# 8x8matrix.net
KiCad netlist of a schematic drawn in EAGLE
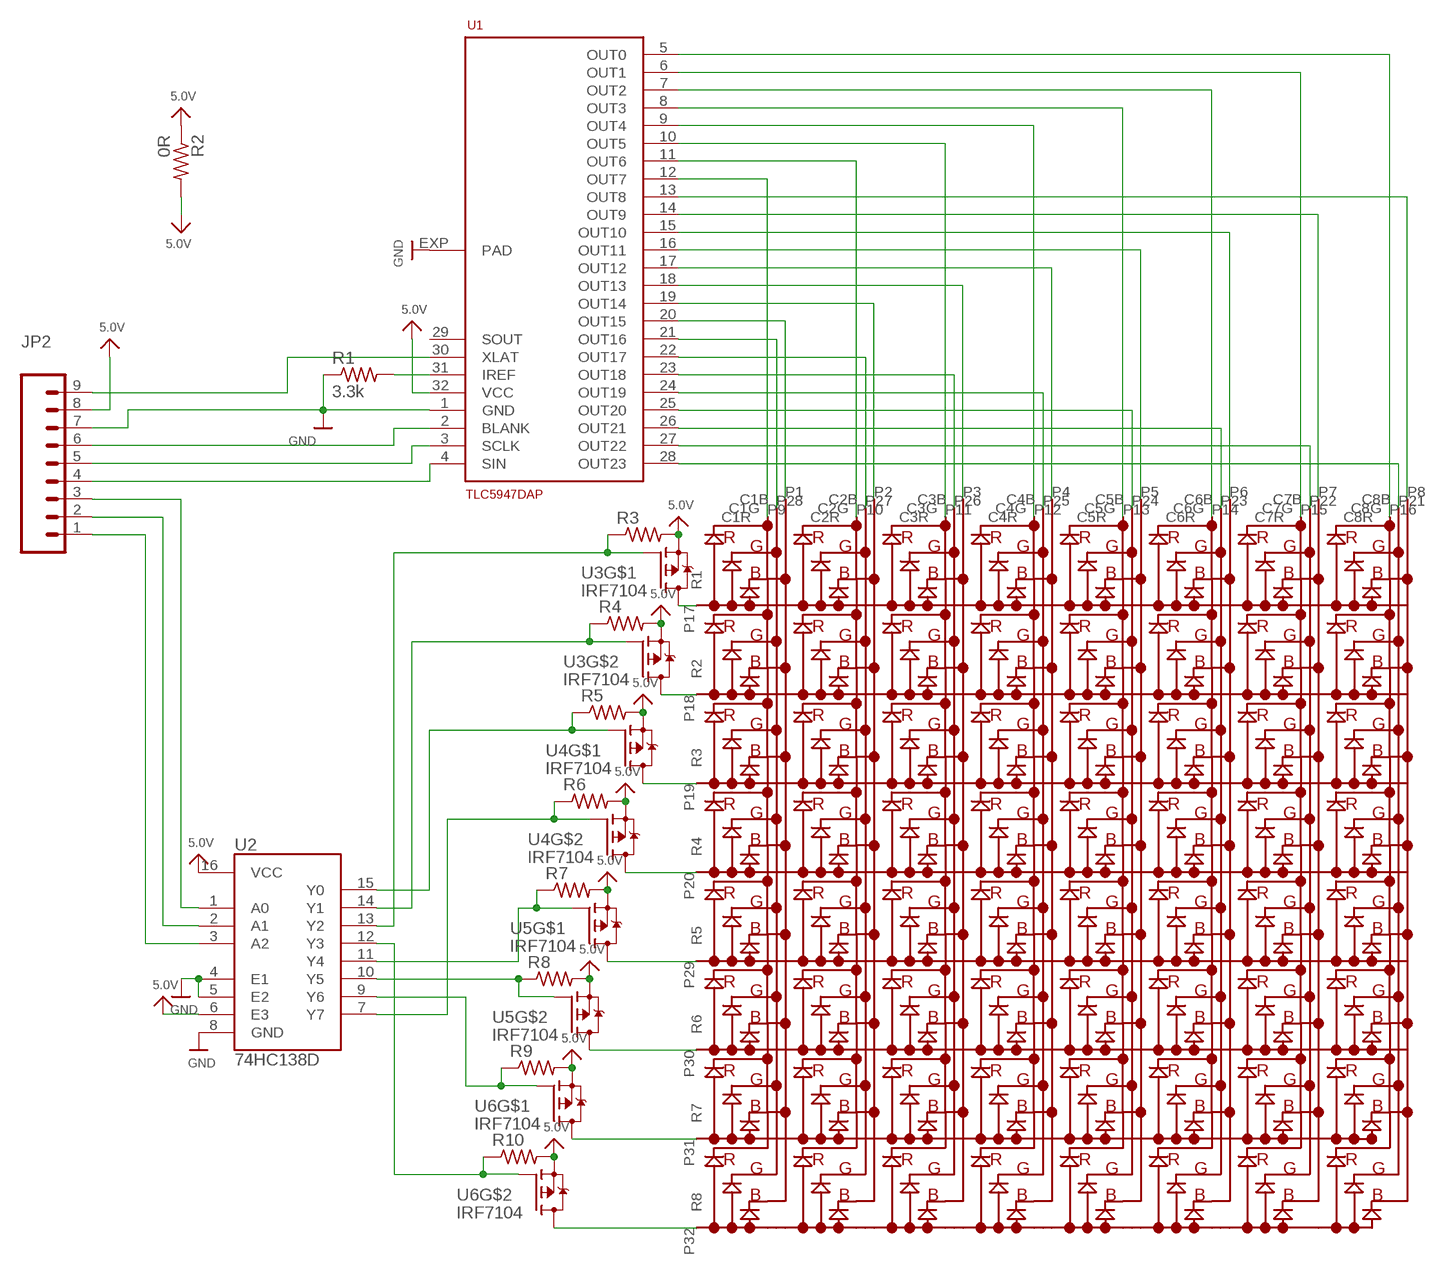
[diagram p0: schematic, sheet 1]

(export (version "E")
  (design (tool "Eeschema 10.0.6"))
  (components
    (comp (ref "JP2")
      (value "M09")
      (footprint "eagle-import:1X09")
      (libsource (lib "eagle-import") (part "M09"))
    )
    (comp (ref "R1")
      (value "3.3k")
      (footprint "eagle-import:R0805")
      (libsource (lib "eagle-import") (part "R-US_R0805"))
    )
    (comp (ref "R2")
      (value "0R")
      (footprint "eagle-import:M1206")
      (libsource (lib "eagle-import") (part "R-US_M1206"))
    )
    (comp (ref "R3")
      (value "R-US_R0805")
      (footprint "eagle-import:R0805")
      (libsource (lib "eagle-import") (part "R-US_R0805"))
    )
    (comp (ref "R4")
      (value "R-US_R0805")
      (footprint "eagle-import:R0805")
      (libsource (lib "eagle-import") (part "R-US_R0805"))
    )
    (comp (ref "R5")
      (value "R-US_R0805")
      (footprint "eagle-import:R0805")
      (libsource (lib "eagle-import") (part "R-US_R0805"))
    )
    (comp (ref "R6")
      (value "R-US_R0805")
      (footprint "eagle-import:R0805")
      (libsource (lib "eagle-import") (part "R-US_R0805"))
    )
    (comp (ref "R7")
      (value "R-US_R0805")
      (footprint "eagle-import:R0805")
      (libsource (lib "eagle-import") (part "R-US_R0805"))
    )
    (comp (ref "R8")
      (value "R-US_R0805")
      (footprint "eagle-import:R0805")
      (libsource (lib "eagle-import") (part "R-US_R0805"))
    )
    (comp (ref "R9")
      (value "R-US_R0805")
      (footprint "eagle-import:R0805")
      (libsource (lib "eagle-import") (part "R-US_R0805"))
    )
    (comp (ref "R10")
      (value "R-US_R0805")
      (footprint "eagle-import:R0805")
      (libsource (lib "eagle-import") (part "R-US_R0805"))
    )
    (comp (ref "U$1")
      (value "GTM2088ARGB")
      (footprint "eagle-import:8X8MATRIX")
      (libsource (lib "eagle-import") (part "GTM2088ARGB"))
    )
    (comp (ref "U1")
      (value "TLC5947DAP")
      (footprint "eagle-import:HTSSOP32DAP")
      (libsource (lib "eagle-import") (part "TLC5947DAP"))
    )
    (comp (ref "U2")
      (value "74HC138D")
      (footprint "eagle-import:SO-16")
      (libsource (lib "eagle-import") (part "74HC138D"))
    )
    (comp (ref "U3")
      (value "IRF7104")
      (footprint "eagle-import:SOIC8")
      (libsource (lib "eagle-import") (part "IRF7104"))
    )
    (comp (ref "U4")
      (value "IRF7104")
      (footprint "eagle-import:SOIC8")
      (libsource (lib "eagle-import") (part "IRF7104"))
    )
    (comp (ref "U5")
      (value "IRF7104")
      (footprint "eagle-import:SOIC8")
      (libsource (lib "eagle-import") (part "IRF7104"))
    )
    (comp (ref "U6")
      (value "IRF7104")
      (footprint "eagle-import:SOIC8")
      (libsource (lib "eagle-import") (part "IRF7104"))
    )
  )
  (nets
    (net (code "1") (name "5.0V") (class "Default")
      (node (ref "JP2") (pin "8") (pinfunction "8_8") (pintype "passive"))
      (node (ref "R10") (pin "2") (pinfunction "2_2") (pintype "passive"))
      (node (ref "R2") (pin "1") (pinfunction "1_1") (pintype "passive"))
      (node (ref "R2") (pin "2") (pinfunction "2_2") (pintype "passive"))
      (node (ref "R3") (pin "2") (pinfunction "2_2") (pintype "passive"))
      (node (ref "R4") (pin "2") (pinfunction "2_2") (pintype "passive"))
      (node (ref "R5") (pin "2") (pinfunction "2_2") (pintype "passive"))
      (node (ref "R6") (pin "2") (pinfunction "2_2") (pintype "passive"))
      (node (ref "R7") (pin "2") (pinfunction "2_2") (pintype "passive"))
      (node (ref "R8") (pin "2") (pinfunction "2_2") (pintype "passive"))
      (node (ref "R9") (pin "2") (pinfunction "2_2") (pintype "passive"))
      (node (ref "U1") (pin "32") (pinfunction "VCC_32") (pintype "bidirectional"))
      (node (ref "U2") (pin "16") (pinfunction "VCC_16") (pintype "bidirectional"))
      (node (ref "U2") (pin "6") (pinfunction "E3_6") (pintype "bidirectional"))
      (node (ref "U3") (pin "1") (pinfunction "S_1") (pintype "passive"))
      (node (ref "U3") (pin "3") (pinfunction "S_3") (pintype "passive"))
      (node (ref "U4") (pin "1") (pinfunction "S_1") (pintype "passive"))
      (node (ref "U4") (pin "3") (pinfunction "S_3") (pintype "passive"))
      (node (ref "U5") (pin "1") (pinfunction "S_1") (pintype "passive"))
      (node (ref "U5") (pin "3") (pinfunction "S_3") (pintype "passive"))
      (node (ref "U6") (pin "1") (pinfunction "S_1") (pintype "passive"))
      (node (ref "U6") (pin "3") (pinfunction "S_3") (pintype "passive"))
    )
    (net (code "2") (name "GND") (class "Default")
      (node (ref "JP2") (pin "7") (pinfunction "7_7") (pintype "passive"))
      (node (ref "R1") (pin "1") (pinfunction "1_1") (pintype "passive"))
      (node (ref "U1") (pin "1") (pinfunction "GND_1") (pintype "bidirectional"))
      (node (ref "U1") (pin "EXP") (pinfunction "PAD_EXP") (pintype "bidirectional"))
      (node (ref "U2") (pin "4") (pinfunction "E1_4") (pintype "bidirectional"))
      (node (ref "U2") (pin "5") (pinfunction "E2_5") (pintype "bidirectional"))
      (node (ref "U2") (pin "8") (pinfunction "GND_8") (pintype "bidirectional"))
    )
    (net (code "3") (name "Net-(U$1-C1B)") (class "Default")
      (node (ref "U$1") (pin "P1") (pinfunction "C1B_P1") (pintype "bidirectional"))
      (node (ref "U1") (pin "20") (pinfunction "OUT15_20") (pintype "bidirectional"))
    )
    (net (code "4") (name "Net-(U$1-C1G)") (class "Default")
      (node (ref "U$1") (pin "P28") (pinfunction "C1G_P28") (pintype "bidirectional"))
      (node (ref "U1") (pin "21") (pinfunction "OUT16_21") (pintype "bidirectional"))
    )
    (net (code "5") (name "Net-(U$1-C1R)") (class "Default")
      (node (ref "U$1") (pin "P9") (pinfunction "C1R_P9") (pintype "bidirectional"))
      (node (ref "U1") (pin "12") (pinfunction "OUT7_12") (pintype "bidirectional"))
    )
    (net (code "6") (name "Net-(U$1-C2B)") (class "Default")
      (node (ref "U$1") (pin "P2") (pinfunction "C2B_P2") (pintype "bidirectional"))
      (node (ref "U1") (pin "19") (pinfunction "OUT14_19") (pintype "bidirectional"))
    )
    (net (code "7") (name "Net-(U$1-C2G)") (class "Default")
      (node (ref "U$1") (pin "P27") (pinfunction "C2G_P27") (pintype "bidirectional"))
      (node (ref "U1") (pin "22") (pinfunction "OUT17_22") (pintype "bidirectional"))
    )
    (net (code "8") (name "Net-(U$1-C2R)") (class "Default")
      (node (ref "U$1") (pin "P10") (pinfunction "C2R_P10") (pintype "bidirectional"))
      (node (ref "U1") (pin "11") (pinfunction "OUT6_11") (pintype "bidirectional"))
    )
    (net (code "9") (name "Net-(U$1-C3B)") (class "Default")
      (node (ref "U$1") (pin "P3") (pinfunction "C3B_P3") (pintype "bidirectional"))
      (node (ref "U1") (pin "18") (pinfunction "OUT13_18") (pintype "bidirectional"))
    )
    (net (code "10") (name "Net-(U$1-C3G)") (class "Default")
      (node (ref "U$1") (pin "P26") (pinfunction "C3G_P26") (pintype "bidirectional"))
      (node (ref "U1") (pin "23") (pinfunction "OUT18_23") (pintype "bidirectional"))
    )
    (net (code "11") (name "Net-(U$1-C3R)") (class "Default")
      (node (ref "U$1") (pin "P11") (pinfunction "C3R_P11") (pintype "bidirectional"))
      (node (ref "U1") (pin "10") (pinfunction "OUT5_10") (pintype "bidirectional"))
    )
    (net (code "12") (name "Net-(U$1-C4B)") (class "Default")
      (node (ref "U$1") (pin "P4") (pinfunction "C4B_P4") (pintype "bidirectional"))
      (node (ref "U1") (pin "17") (pinfunction "OUT12_17") (pintype "bidirectional"))
    )
    (net (code "13") (name "Net-(U$1-C4G)") (class "Default")
      (node (ref "U$1") (pin "P25") (pinfunction "C4G_P25") (pintype "bidirectional"))
      (node (ref "U1") (pin "24") (pinfunction "OUT19_24") (pintype "bidirectional"))
    )
    (net (code "14") (name "Net-(U$1-C4R)") (class "Default")
      (node (ref "U$1") (pin "P12") (pinfunction "C4R_P12") (pintype "bidirectional"))
      (node (ref "U1") (pin "9") (pinfunction "OUT4_9") (pintype "bidirectional"))
    )
    (net (code "15") (name "Net-(U$1-C5B)") (class "Default")
      (node (ref "U$1") (pin "P5") (pinfunction "C5B_P5") (pintype "bidirectional"))
      (node (ref "U1") (pin "16") (pinfunction "OUT11_16") (pintype "bidirectional"))
    )
    (net (code "16") (name "Net-(U$1-C5G)") (class "Default")
      (node (ref "U$1") (pin "P24") (pinfunction "C5G_P24") (pintype "bidirectional"))
      (node (ref "U1") (pin "25") (pinfunction "OUT20_25") (pintype "bidirectional"))
    )
    (net (code "17") (name "Net-(U$1-C5R)") (class "Default")
      (node (ref "U$1") (pin "P13") (pinfunction "C5R_P13") (pintype "bidirectional"))
      (node (ref "U1") (pin "8") (pinfunction "OUT3_8") (pintype "bidirectional"))
    )
    (net (code "18") (name "Net-(U$1-C6B)") (class "Default")
      (node (ref "U$1") (pin "P6") (pinfunction "C6B_P6") (pintype "bidirectional"))
      (node (ref "U1") (pin "15") (pinfunction "OUT10_15") (pintype "bidirectional"))
    )
    (net (code "19") (name "Net-(U$1-C6G)") (class "Default")
      (node (ref "U$1") (pin "P23") (pinfunction "C6G_P23") (pintype "bidirectional"))
      (node (ref "U1") (pin "26") (pinfunction "OUT21_26") (pintype "bidirectional"))
    )
    (net (code "20") (name "Net-(U$1-C6R)") (class "Default")
      (node (ref "U$1") (pin "P14") (pinfunction "C6R_P14") (pintype "bidirectional"))
      (node (ref "U1") (pin "7") (pinfunction "OUT2_7") (pintype "bidirectional"))
    )
    (net (code "21") (name "Net-(U$1-C7B)") (class "Default")
      (node (ref "U$1") (pin "P7") (pinfunction "C7B_P7") (pintype "bidirectional"))
      (node (ref "U1") (pin "14") (pinfunction "OUT9_14") (pintype "bidirectional"))
    )
    (net (code "22") (name "Net-(U$1-C7G)") (class "Default")
      (node (ref "U$1") (pin "P22") (pinfunction "C7G_P22") (pintype "bidirectional"))
      (node (ref "U1") (pin "27") (pinfunction "OUT22_27") (pintype "bidirectional"))
    )
    (net (code "23") (name "Net-(U$1-C7R)") (class "Default")
      (node (ref "U$1") (pin "P15") (pinfunction "C7R_P15") (pintype "bidirectional"))
      (node (ref "U1") (pin "6") (pinfunction "OUT1_6") (pintype "bidirectional"))
    )
    (net (code "24") (name "Net-(U$1-C8B)") (class "Default")
      (node (ref "U$1") (pin "P8") (pinfunction "C8B_P8") (pintype "bidirectional"))
      (node (ref "U1") (pin "13") (pinfunction "OUT8_13") (pintype "bidirectional"))
    )
    (net (code "25") (name "Net-(U$1-C8G)") (class "Default")
      (node (ref "U$1") (pin "P21") (pinfunction "C8G_P21") (pintype "bidirectional"))
      (node (ref "U1") (pin "28") (pinfunction "OUT23_28") (pintype "bidirectional"))
    )
    (net (code "26") (name "Net-(U$1-C8R)") (class "Default")
      (node (ref "U$1") (pin "P16") (pinfunction "C8R_P16") (pintype "bidirectional"))
      (node (ref "U1") (pin "5") (pinfunction "OUT0_5") (pintype "bidirectional"))
    )
    (net (code "27") (name "Net-(U$1-R1)") (class "Default")
      (node (ref "U$1") (pin "P17") (pinfunction "R1_P17") (pintype "bidirectional"))
      (node (ref "U3") (pin "7") (pinfunction "D_7") (pintype "passive"))
      (node (ref "U3") (pin "8") (pinfunction "D_8") (pintype "passive"))
    )
    (net (code "28") (name "Net-(U$1-R2)") (class "Default")
      (node (ref "U$1") (pin "P18") (pinfunction "R2_P18") (pintype "bidirectional"))
      (node (ref "U3") (pin "5") (pinfunction "D_5") (pintype "passive"))
      (node (ref "U3") (pin "6") (pinfunction "D_6") (pintype "passive"))
    )
    (net (code "29") (name "Net-(U$1-R3)") (class "Default")
      (node (ref "U$1") (pin "P19") (pinfunction "R3_P19") (pintype "bidirectional"))
      (node (ref "U4") (pin "7") (pinfunction "D_7") (pintype "passive"))
      (node (ref "U4") (pin "8") (pinfunction "D_8") (pintype "passive"))
    )
    (net (code "30") (name "Net-(U$1-R4)") (class "Default")
      (node (ref "U$1") (pin "P20") (pinfunction "R4_P20") (pintype "bidirectional"))
      (node (ref "U4") (pin "5") (pinfunction "D_5") (pintype "passive"))
      (node (ref "U4") (pin "6") (pinfunction "D_6") (pintype "passive"))
    )
    (net (code "31") (name "Net-(U$1-R5)") (class "Default")
      (node (ref "U$1") (pin "P29") (pinfunction "R5_P29") (pintype "bidirectional"))
      (node (ref "U5") (pin "7") (pinfunction "D_7") (pintype "passive"))
      (node (ref "U5") (pin "8") (pinfunction "D_8") (pintype "passive"))
    )
    (net (code "32") (name "Net-(U$1-R6)") (class "Default")
      (node (ref "U$1") (pin "P30") (pinfunction "R6_P30") (pintype "bidirectional"))
      (node (ref "U5") (pin "5") (pinfunction "D_5") (pintype "passive"))
      (node (ref "U5") (pin "6") (pinfunction "D_6") (pintype "passive"))
    )
    (net (code "33") (name "Net-(U$1-R7)") (class "Default")
      (node (ref "U$1") (pin "P31") (pinfunction "R7_P31") (pintype "bidirectional"))
      (node (ref "U6") (pin "7") (pinfunction "D_7") (pintype "passive"))
      (node (ref "U6") (pin "8") (pinfunction "D_8") (pintype "passive"))
    )
    (net (code "34") (name "Net-(U$1-R8)") (class "Default")
      (node (ref "U$1") (pin "P32") (pinfunction "R8_P32") (pintype "bidirectional"))
      (node (ref "U6") (pin "5") (pinfunction "D_5") (pintype "passive"))
      (node (ref "U6") (pin "6") (pinfunction "D_6") (pintype "passive"))
    )
    (net (code "35") (name "Net-(U1-BLANK)") (class "Default")
      (node (ref "JP2") (pin "6") (pinfunction "6_6") (pintype "passive"))
      (node (ref "U1") (pin "2") (pinfunction "BLANK_2") (pintype "bidirectional"))
    )
    (net (code "36") (name "Net-(U1-IREF)") (class "Default")
      (node (ref "R1") (pin "2") (pinfunction "2_2") (pintype "passive"))
      (node (ref "U1") (pin "31") (pinfunction "IREF_31") (pintype "bidirectional"))
    )
    (net (code "37") (name "Net-(U1-SCLK)") (class "Default")
      (node (ref "JP2") (pin "5") (pinfunction "5_5") (pintype "passive"))
      (node (ref "U1") (pin "3") (pinfunction "SCLK_3") (pintype "bidirectional"))
    )
    (net (code "38") (name "Net-(U1-SIN)") (class "Default")
      (node (ref "JP2") (pin "4") (pinfunction "4_4") (pintype "passive"))
      (node (ref "U1") (pin "4") (pinfunction "SIN_4") (pintype "bidirectional"))
    )
    (net (code "39") (name "Net-(U1-XLAT)") (class "Default")
      (node (ref "JP2") (pin "9") (pinfunction "9_9") (pintype "passive"))
      (node (ref "U1") (pin "30") (pinfunction "XLAT_30") (pintype "bidirectional"))
    )
    (net (code "40") (name "Net-(U2-A0)") (class "Default")
      (node (ref "JP2") (pin "3") (pinfunction "3_3") (pintype "passive"))
      (node (ref "U2") (pin "1") (pinfunction "A0_1") (pintype "bidirectional"))
    )
    (net (code "41") (name "Net-(U2-A1)") (class "Default")
      (node (ref "JP2") (pin "2") (pinfunction "2_2") (pintype "passive"))
      (node (ref "U2") (pin "2") (pinfunction "A1_2") (pintype "bidirectional"))
    )
    (net (code "42") (name "Net-(U2-A2)") (class "Default")
      (node (ref "JP2") (pin "1") (pinfunction "1_1") (pintype "passive"))
      (node (ref "U2") (pin "3") (pinfunction "A2_3") (pintype "bidirectional"))
    )
    (net (code "43") (name "Net-(U2-Y0)") (class "Default")
      (node (ref "R5") (pin "1") (pinfunction "1_1") (pintype "passive"))
      (node (ref "U2") (pin "15") (pinfunction "Y0_15") (pintype "bidirectional"))
      (node (ref "U4") (pin "2") (pinfunction "G_2") (pintype "passive"))
    )
    (net (code "44") (name "Net-(U2-Y1)") (class "Default")
      (node (ref "R4") (pin "1") (pinfunction "1_1") (pintype "passive"))
      (node (ref "U2") (pin "14") (pinfunction "Y1_14") (pintype "bidirectional"))
      (node (ref "U3") (pin "4") (pinfunction "G_4") (pintype "passive"))
    )
    (net (code "45") (name "Net-(U2-Y2)") (class "Default")
      (node (ref "R3") (pin "1") (pinfunction "1_1") (pintype "passive"))
      (node (ref "U2") (pin "13") (pinfunction "Y2_13") (pintype "bidirectional"))
      (node (ref "U3") (pin "2") (pinfunction "G_2") (pintype "passive"))
    )
    (net (code "46") (name "Net-(U2-Y3)") (class "Default")
      (node (ref "R10") (pin "1") (pinfunction "1_1") (pintype "passive"))
      (node (ref "U2") (pin "12") (pinfunction "Y3_12") (pintype "bidirectional"))
      (node (ref "U6") (pin "4") (pinfunction "G_4") (pintype "passive"))
    )
    (net (code "47") (name "Net-(U2-Y4)") (class "Default")
      (node (ref "R7") (pin "1") (pinfunction "1_1") (pintype "passive"))
      (node (ref "U2") (pin "11") (pinfunction "Y4_11") (pintype "bidirectional"))
      (node (ref "U5") (pin "2") (pinfunction "G_2") (pintype "passive"))
    )
    (net (code "48") (name "Net-(U2-Y5)") (class "Default")
      (node (ref "R8") (pin "1") (pinfunction "1_1") (pintype "passive"))
      (node (ref "U2") (pin "10") (pinfunction "Y5_10") (pintype "bidirectional"))
      (node (ref "U5") (pin "4") (pinfunction "G_4") (pintype "passive"))
    )
    (net (code "49") (name "Net-(U2-Y6)") (class "Default")
      (node (ref "R9") (pin "1") (pinfunction "1_1") (pintype "passive"))
      (node (ref "U2") (pin "9") (pinfunction "Y6_9") (pintype "bidirectional"))
      (node (ref "U6") (pin "2") (pinfunction "G_2") (pintype "passive"))
    )
    (net (code "50") (name "Net-(U2-Y7)") (class "Default")
      (node (ref "R6") (pin "1") (pinfunction "1_1") (pintype "passive"))
      (node (ref "U2") (pin "7") (pinfunction "Y7_7") (pintype "bidirectional"))
      (node (ref "U4") (pin "4") (pinfunction "G_4") (pintype "passive"))
    )
    (net (code "51") (name "unconnected-(U1-SOUT-Pad29)") (class "Default")
      (node (ref "U1") (pin "29") (pinfunction "SOUT_29") (pintype "bidirectional"))
    )
  )
)
